# SENSOR.net
KiCad netlist of a schematic drawn in Altium Designer
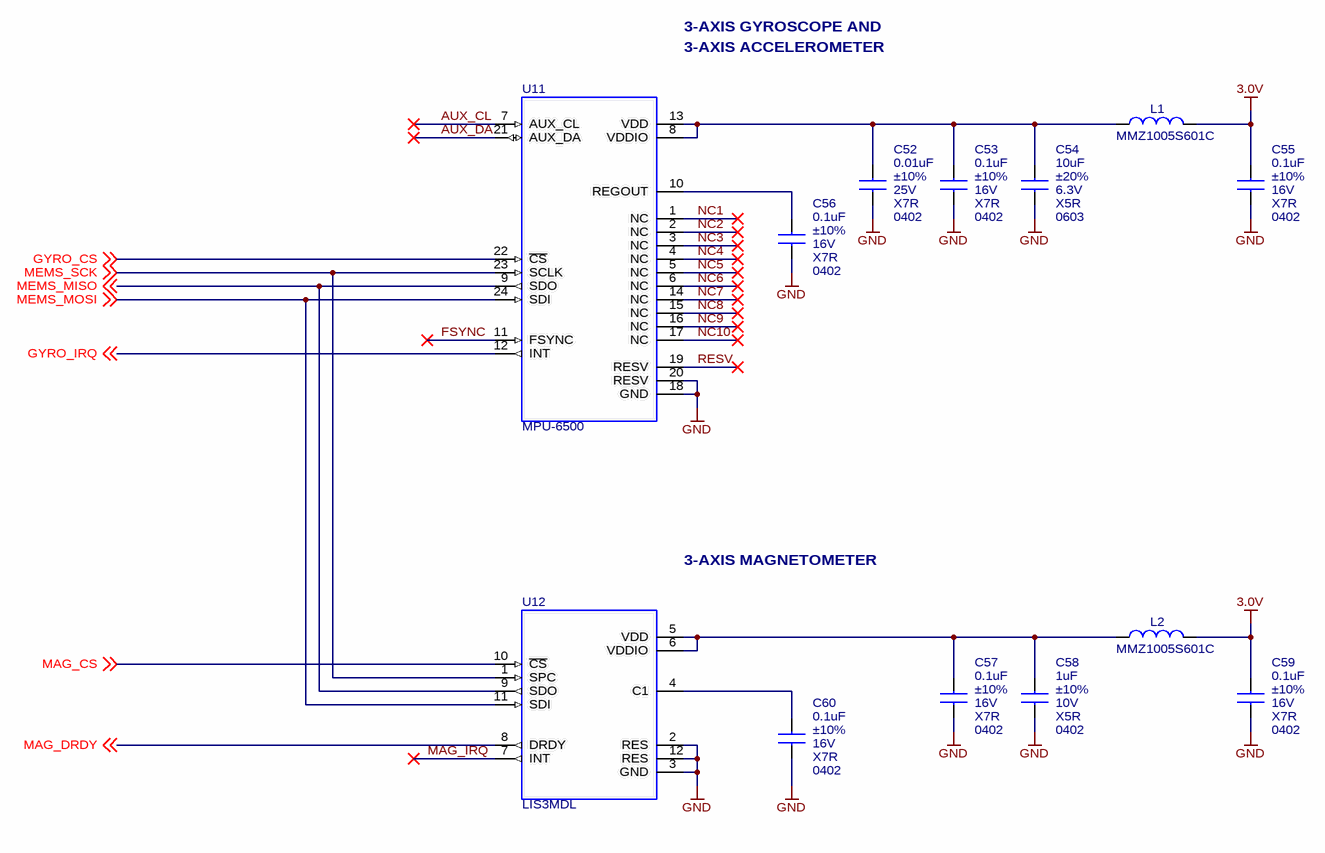
[diagram p0: SENSOR.SchDoc]

(export (version "E")
  (design (tool "Eeschema 10.0.6"))
  (components
    (comp (ref "C52")
      (value "0.01uF")
      (footprint "CAP_CERAMIC_0402")
      (description "CAP, CERAMIC, 0.01uF, ±10%, 25V, X7R, 0402")
      (fields
        (field (name "MANUFACTURER") "MURATA ELECTRONICS")
        (field (name "PART NUMBER") "GRM155R71E103KA01D")
        (field (name "TOLERANCE") "±10%")
        (field (name "VOLTAGE") "25V")
        (field (name "DIELECTRIC") "X7R")
        (field (name "PACKAGE") "0402")
      )
      (libsource (lib "DK2") (part "CAP, CERAMIC"))
    )
    (comp (ref "C53")
      (value "0.1uF")
      (footprint "CAP_CERAMIC_0402")
      (description "CAP, CERAMIC, 0.1uF, ±10%, 16V, X7R, 0402")
      (fields
        (field (name "MANUFACTURER") "MURATA ELECTRONICS")
        (field (name "PART NUMBER") "GRM155R71C104KA88D")
        (field (name "TOLERANCE") "±10%")
        (field (name "VOLTAGE") "16V")
        (field (name "DIELECTRIC") "X7R")
        (field (name "PACKAGE") "0402")
      )
      (libsource (lib "DK2") (part "CAP, CERAMIC"))
    )
    (comp (ref "C54")
      (value "10uF")
      (footprint "CAP_CERAMIC_0603")
      (description "CAP, CERAMIC, 10uF, ±20%, 6.3V, X5R, 0603")
      (fields
        (field (name "MANUFACTURER") "MURATA ELECTRONICS")
        (field (name "PART NUMBER") "GRM188R60J106ME47D")
        (field (name "TOLERANCE") "±20%")
        (field (name "VOLTAGE") "6.3V")
        (field (name "DIELECTRIC") "X5R")
        (field (name "PACKAGE") "0603")
      )
      (libsource (lib "DK2") (part "CAP, CERAMIC"))
    )
    (comp (ref "C55")
      (value "0.1uF")
      (footprint "CAP_CERAMIC_0402")
      (description "CAP, CERAMIC, 0.1uF, ±10%, 16V, X7R, 0402")
      (fields
        (field (name "MANUFACTURER") "MURATA ELECTRONICS")
        (field (name "PART NUMBER") "GRM155R71C104KA88D")
        (field (name "TOLERANCE") "±10%")
        (field (name "VOLTAGE") "16V")
        (field (name "DIELECTRIC") "X7R")
        (field (name "PACKAGE") "0402")
      )
      (libsource (lib "DK2") (part "CAP, CERAMIC"))
    )
    (comp (ref "C56")
      (value "0.1uF")
      (footprint "CAP_CERAMIC_0402")
      (description "CAP, CERAMIC, 0.1uF, ±10%, 16V, X7R, 0402")
      (fields
        (field (name "MANUFACTURER") "MURATA ELECTRONICS")
        (field (name "PART NUMBER") "GRM155R71C104KA88D")
        (field (name "TOLERANCE") "±10%")
        (field (name "VOLTAGE") "16V")
        (field (name "DIELECTRIC") "X7R")
        (field (name "PACKAGE") "0402")
      )
      (libsource (lib "DK2") (part "CAP, CERAMIC"))
    )
    (comp (ref "C57")
      (value "0.1uF")
      (footprint "CAP_CERAMIC_0402")
      (description "CAP, CERAMIC, 0.1uF, ±10%, 16V, X7R, 0402")
      (fields
        (field (name "MANUFACTURER") "MURATA ELECTRONICS")
        (field (name "PART NUMBER") "GRM155R71C104KA88D")
        (field (name "TOLERANCE") "±10%")
        (field (name "VOLTAGE") "16V")
        (field (name "DIELECTRIC") "X7R")
        (field (name "PACKAGE") "0402")
      )
      (libsource (lib "DK2") (part "CAP, CERAMIC"))
    )
    (comp (ref "C58")
      (value "1uF")
      (footprint "CAP_CERAMIC_0402")
      (description "CAP, CERAMIC, 1uF, ±10%, 10V, X5R, 0402")
      (fields
        (field (name "MANUFACTURER") "MURATA ELECTRONICS")
        (field (name "PART NUMBER") "GRM155R61A105KE15D")
        (field (name "TOLERANCE") "±10%")
        (field (name "VOLTAGE") "10V")
        (field (name "DIELECTRIC") "X5R")
        (field (name "PACKAGE") "0402")
      )
      (libsource (lib "DK2") (part "CAP, CERAMIC"))
    )
    (comp (ref "C59")
      (value "0.1uF")
      (footprint "CAP_CERAMIC_0402")
      (description "CAP, CERAMIC, 0.1uF, ±10%, 16V, X7R, 0402")
      (fields
        (field (name "MANUFACTURER") "MURATA ELECTRONICS")
        (field (name "PART NUMBER") "GRM155R71C104KA88D")
        (field (name "TOLERANCE") "±10%")
        (field (name "VOLTAGE") "16V")
        (field (name "DIELECTRIC") "X7R")
        (field (name "PACKAGE") "0402")
      )
      (libsource (lib "DK2") (part "CAP, CERAMIC"))
    )
    (comp (ref "C60")
      (value "0.1uF")
      (footprint "CAP_CERAMIC_0402")
      (description "CAP, CERAMIC, 0.1uF, ±10%, 16V, X7R, 0402")
      (fields
        (field (name "MANUFACTURER") "MURATA ELECTRONICS")
        (field (name "PART NUMBER") "GRM155R71C104KA88D")
        (field (name "TOLERANCE") "±10%")
        (field (name "VOLTAGE") "16V")
        (field (name "DIELECTRIC") "X7R")
        (field (name "PACKAGE") "0402")
      )
      (libsource (lib "DK2") (part "CAP, CERAMIC"))
    )
    (comp (ref "L1")
      (value "MMZ1005S601C")
      (footprint "INDUCTOR_0402")
      (description "FERRITE CHIP BEAD, 600 OHM @ 100MHz, 300mA, 0402")
      (fields (field (name "MANUFACTURER") "TDK CORPORATION"))
      (libsource (lib "DK2") (part "INDUCTOR"))
    )
    (comp (ref "L2")
      (value "MMZ1005S601C")
      (footprint "INDUCTOR_0402")
      (description "FERRITE CHIP BEAD, 600 OHM @ 100MHz, 300mA, 0402")
      (fields (field (name "MANUFACTURER") "TDK CORPORATION"))
      (libsource (lib "DK2") (part "INDUCTOR"))
    )
    (comp (ref "U11")
      (value "MPU-6500")
      (footprint "QFN-24")
      (description "IC, MEMS 3 AXIS GYROSCOPE AND 3 AXIS ACCELEROMETER")
      (fields (field (name "MANUFACTURER") "INVENSENSE"))
      (libsource (lib "DK2") (part "MPU-6500"))
    )
    (comp (ref "U12")
      (value "LIS3MDL")
      (footprint "LGA-12")
      (description "IC, MEMS 3 AXIS MAGNETOMETER")
      (fields (field (name "MANUFACTURER") "STMICROELECTRONICS") (field (name "PART NUMBER") "LIS3MDLTR"))
      (libsource (lib "DK2") (part "LIS3MDL"))
    )
  )
  (nets
    (net (code "1") (name "/AUX_CL") (class "Default")
      (node (ref "U11") (pin "7") (pinfunction "AUX_CL_7") (pintype "input+no_connect"))
    )
    (net (code "2") (name "/AUX_DA") (class "Default")
      (node (ref "U11") (pin "21") (pinfunction "AUX_DA_21") (pintype "bidirectional+no_connect"))
    )
    (net (code "3") (name "/FSYNC") (class "Default")
      (node (ref "U11") (pin "11") (pinfunction "FSYNC_11") (pintype "input+no_connect"))
    )
    (net (code "4") (name "/MAG_IRQ") (class "Default")
      (node (ref "U12") (pin "7") (pinfunction "INT_7") (pintype "output+no_connect"))
    )
    (net (code "5") (name "/NC1") (class "Default")
      (node (ref "U11") (pin "1") (pinfunction "NC_1") (pintype "passive+no_connect"))
    )
    (net (code "6") (name "/NC2") (class "Default")
      (node (ref "U11") (pin "2") (pinfunction "NC_2") (pintype "passive+no_connect"))
    )
    (net (code "7") (name "/NC3") (class "Default")
      (node (ref "U11") (pin "3") (pinfunction "NC_3") (pintype "passive+no_connect"))
    )
    (net (code "8") (name "/NC4") (class "Default")
      (node (ref "U11") (pin "4") (pinfunction "NC_4") (pintype "passive+no_connect"))
    )
    (net (code "9") (name "/NC5") (class "Default")
      (node (ref "U11") (pin "5") (pinfunction "NC_5") (pintype "passive+no_connect"))
    )
    (net (code "10") (name "/NC6") (class "Default")
      (node (ref "U11") (pin "6") (pinfunction "NC_6") (pintype "passive+no_connect"))
    )
    (net (code "11") (name "/NC7") (class "Default")
      (node (ref "U11") (pin "14") (pinfunction "NC_14") (pintype "passive+no_connect"))
    )
    (net (code "12") (name "/NC8") (class "Default")
      (node (ref "U11") (pin "15") (pinfunction "NC_15") (pintype "passive+no_connect"))
    )
    (net (code "13") (name "/NC9") (class "Default")
      (node (ref "U11") (pin "16") (pinfunction "NC_16") (pintype "passive+no_connect"))
    )
    (net (code "14") (name "/NC10") (class "Default")
      (node (ref "U11") (pin "17") (pinfunction "NC_17") (pintype "passive+no_connect"))
    )
    (net (code "15") (name "/RESV") (class "Default")
      (node (ref "U11") (pin "19") (pinfunction "RESV_19") (pintype "passive+no_connect"))
    )
    (net (code "16") (name "3.0V") (class "Default")
      (node (ref "C55") (pin "1") (pinfunction "1_1") (pintype "passive"))
      (node (ref "C59") (pin "1") (pinfunction "1_1") (pintype "passive"))
      (node (ref "L1") (pin "2") (pinfunction "2_2") (pintype "passive"))
      (node (ref "L2") (pin "2") (pinfunction "2_2") (pintype "passive"))
    )
    (net (code "17") (name "GND") (class "Default")
      (node (ref "C52") (pin "2") (pinfunction "2_2") (pintype "passive"))
      (node (ref "C53") (pin "2") (pinfunction "2_2") (pintype "passive"))
      (node (ref "C54") (pin "2") (pinfunction "2_2") (pintype "passive"))
      (node (ref "C55") (pin "2") (pinfunction "2_2") (pintype "passive"))
      (node (ref "C56") (pin "2") (pinfunction "2_2") (pintype "passive"))
      (node (ref "C57") (pin "2") (pinfunction "2_2") (pintype "passive"))
      (node (ref "C58") (pin "2") (pinfunction "2_2") (pintype "passive"))
      (node (ref "C59") (pin "2") (pinfunction "2_2") (pintype "passive"))
      (node (ref "C60") (pin "2") (pinfunction "2_2") (pintype "passive"))
      (node (ref "U11") (pin "18") (pinfunction "GND_18") (pintype "power_in"))
      (node (ref "U11") (pin "20") (pinfunction "RESV_20") (pintype "passive"))
      (node (ref "U12") (pin "12") (pinfunction "RES_12") (pintype "passive"))
      (node (ref "U12") (pin "2") (pinfunction "RES_2") (pintype "passive"))
      (node (ref "U12") (pin "3") (pinfunction "GND_3") (pintype "power_in"))
    )
    (net (code "18") (name "GYRO_CS") (class "Default")
      (node (ref "U11") (pin "22") (pinfunction "~{CS}_22") (pintype "input"))
    )
    (net (code "19") (name "GYRO_IRQ") (class "Default")
      (node (ref "U11") (pin "12") (pinfunction "INT_12") (pintype "output"))
    )
    (net (code "20") (name "MAG_CS") (class "Default")
      (node (ref "U12") (pin "10") (pinfunction "~{CS}_10") (pintype "input"))
    )
    (net (code "21") (name "MAG_DRDY") (class "Default")
      (node (ref "U12") (pin "8") (pinfunction "DRDY_8") (pintype "output"))
    )
    (net (code "22") (name "MEMS_MISO") (class "Default")
      (node (ref "U11") (pin "9") (pinfunction "SDO_9") (pintype "output"))
      (node (ref "U12") (pin "9") (pinfunction "SDO_9") (pintype "output"))
    )
    (net (code "23") (name "MEMS_MOSI") (class "Default")
      (node (ref "U11") (pin "24") (pinfunction "SDI_24") (pintype "input"))
      (node (ref "U12") (pin "11") (pinfunction "SDI_11") (pintype "input"))
    )
    (net (code "24") (name "MEMS_SCK") (class "Default")
      (node (ref "U11") (pin "23") (pinfunction "SCLK_23") (pintype "input"))
      (node (ref "U12") (pin "1") (pinfunction "SPC_1") (pintype "input"))
    )
    (net (code "25") (name "Net-(U11-REGOUT)") (class "Default")
      (node (ref "C56") (pin "1") (pinfunction "1_1") (pintype "passive"))
      (node (ref "U11") (pin "10") (pinfunction "REGOUT_10") (pintype "power_in"))
    )
    (net (code "26") (name "Net-(U11-VDD)") (class "Default")
      (node (ref "C52") (pin "1") (pinfunction "1_1") (pintype "passive"))
      (node (ref "C53") (pin "1") (pinfunction "1_1") (pintype "passive"))
      (node (ref "C54") (pin "1") (pinfunction "1_1") (pintype "passive"))
      (node (ref "L1") (pin "1") (pinfunction "1_1") (pintype "passive"))
      (node (ref "U11") (pin "13") (pinfunction "VDD_13") (pintype "power_in"))
      (node (ref "U11") (pin "8") (pinfunction "VDDIO_8") (pintype "power_in"))
    )
    (net (code "27") (name "Net-(U12-C1)") (class "Default")
      (node (ref "C60") (pin "1") (pinfunction "1_1") (pintype "passive"))
      (node (ref "U12") (pin "4") (pinfunction "C1_4") (pintype "passive"))
    )
    (net (code "28") (name "Net-(U12-VDD)") (class "Default")
      (node (ref "C57") (pin "1") (pinfunction "1_1") (pintype "passive"))
      (node (ref "C58") (pin "1") (pinfunction "1_1") (pintype "passive"))
      (node (ref "L2") (pin "1") (pinfunction "1_1") (pintype "passive"))
      (node (ref "U12") (pin "5") (pinfunction "VDD_5") (pintype "power_in"))
      (node (ref "U12") (pin "6") (pinfunction "VDDIO_6") (pintype "power_in"))
    )
  )
)
